# 04_InterfaceSensor.net
KiCad netlist of a schematic drawn in Altium Designer
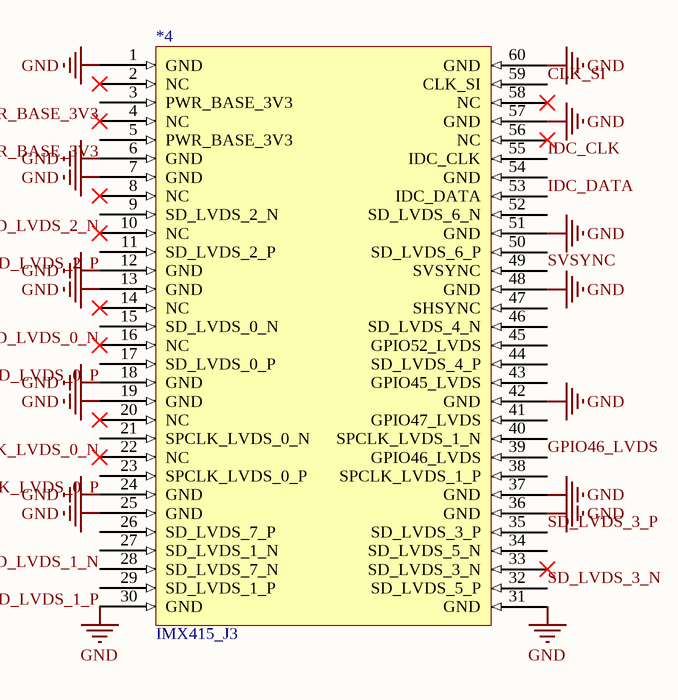
[diagram p0: 04_InterfaceSensor.SchDoc]

(export (version "E")
  (design (tool "Eeschema 10.0.6"))
  (components
    (comp (ref "*4")
      (value "IMX415_J3")
      (footprint "HRS_DF40HC(4.0)-60DS-0.4V(51)")
      (libsource (lib "MyLib") (part "IMX415_J3"))
    )
  )
  (nets
    (net (code "1") (name "/CLK_SI") (class "Default")
      (node (ref "*4") (pin "59") (pinfunction "CLK_SI_59") (pintype "input"))
    )
    (net (code "2") (name "/GPIO46_LVDS") (class "Default")
      (node (ref "*4") (pin "39") (pinfunction "GPIO46_LVDS_39") (pintype "input"))
    )
    (net (code "3") (name "/IDC_CLK") (class "Default")
      (node (ref "*4") (pin "55") (pinfunction "IDC_CLK_55") (pintype "input"))
    )
    (net (code "4") (name "/IDC_DATA") (class "Default")
      (node (ref "*4") (pin "53") (pinfunction "IDC_DATA_53") (pintype "input"))
    )
    (net (code "5") (name "/PWR_BASE_3V3") (class "Default")
      (node (ref "*4") (pin "3") (pinfunction "PWR_BASE_3V3_3") (pintype "input"))
      (node (ref "*4") (pin "5") (pinfunction "PWR_BASE_3V3_5") (pintype "input"))
    )
    (net (code "6") (name "/SD_LVDS_0_N") (class "Default")
      (node (ref "*4") (pin "15") (pinfunction "SD_LVDS_0_N_15") (pintype "input"))
    )
    (net (code "7") (name "/SD_LVDS_0_P") (class "Default")
      (node (ref "*4") (pin "17") (pinfunction "SD_LVDS_0_P_17") (pintype "input"))
    )
    (net (code "8") (name "/SD_LVDS_1_N") (class "Default")
      (node (ref "*4") (pin "27") (pinfunction "SD_LVDS_1_N_27") (pintype "input"))
    )
    (net (code "9") (name "/SD_LVDS_1_P") (class "Default")
      (node (ref "*4") (pin "29") (pinfunction "SD_LVDS_1_P_29") (pintype "input"))
    )
    (net (code "10") (name "/SD_LVDS_2_N") (class "Default")
      (node (ref "*4") (pin "9") (pinfunction "SD_LVDS_2_N_9") (pintype "input"))
    )
    (net (code "11") (name "/SD_LVDS_2_P") (class "Default")
      (node (ref "*4") (pin "11") (pinfunction "SD_LVDS_2_P_11") (pintype "input"))
    )
    (net (code "12") (name "/SD_LVDS_3_N") (class "Default")
      (node (ref "*4") (pin "32") (pinfunction "SD_LVDS_5_P_32") (pintype "input"))
    )
    (net (code "13") (name "/SD_LVDS_3_P") (class "Default")
      (node (ref "*4") (pin "35") (pinfunction "SD_LVDS_3_P_35") (pintype "input"))
    )
    (net (code "14") (name "/SPCLK_LVDS_0_N") (class "Default")
      (node (ref "*4") (pin "21") (pinfunction "SPCLK_LVDS_0_N_21") (pintype "input"))
    )
    (net (code "15") (name "/SPCLK_LVDS_0_P") (class "Default")
      (node (ref "*4") (pin "23") (pinfunction "SPCLK_LVDS_0_P_23") (pintype "input"))
    )
    (net (code "16") (name "/SVSYNC") (class "Default")
      (node (ref "*4") (pin "49") (pinfunction "SVSYNC_49") (pintype "input"))
    )
    (net (code "17") (name "GND") (class "Default")
      (node (ref "*4") (pin "1") (pinfunction "GND_1") (pintype "input"))
      (node (ref "*4") (pin "12") (pinfunction "GND_12") (pintype "input"))
      (node (ref "*4") (pin "13") (pinfunction "GND_13") (pintype "input"))
      (node (ref "*4") (pin "18") (pinfunction "GND_18") (pintype "input"))
      (node (ref "*4") (pin "19") (pinfunction "GND_19") (pintype "input"))
      (node (ref "*4") (pin "24") (pinfunction "GND_24") (pintype "input"))
      (node (ref "*4") (pin "25") (pinfunction "GND_25") (pintype "input"))
      (node (ref "*4") (pin "30") (pinfunction "GND_30") (pintype "input"))
      (node (ref "*4") (pin "31") (pinfunction "GND_31") (pintype "input"))
      (node (ref "*4") (pin "36") (pinfunction "GND_36") (pintype "input"))
      (node (ref "*4") (pin "37") (pinfunction "GND_37") (pintype "input"))
      (node (ref "*4") (pin "42") (pinfunction "GND_42") (pintype "input"))
      (node (ref "*4") (pin "48") (pinfunction "GND_48") (pintype "input"))
      (node (ref "*4") (pin "51") (pinfunction "GND_51") (pintype "input"))
      (node (ref "*4") (pin "57") (pinfunction "GND_57") (pintype "input"))
      (node (ref "*4") (pin "6") (pinfunction "GND_6") (pintype "input"))
      (node (ref "*4") (pin "60") (pinfunction "GND_60") (pintype "input"))
      (node (ref "*4") (pin "7") (pinfunction "GND_7") (pintype "input"))
    )
    (net (code "18") (name "unconnected-(*4-GND-Pad54)") (class "Default")
      (node (ref "*4") (pin "54") (pinfunction "GND_54") (pintype "input"))
    )
    (net (code "19") (name "unconnected-(*4-GPIO45_LVDS-Pad43)") (class "Default")
      (node (ref "*4") (pin "43") (pinfunction "GPIO45_LVDS_43") (pintype "input"))
    )
    (net (code "20") (name "unconnected-(*4-GPIO47_LVDS-Pad41)") (class "Default")
      (node (ref "*4") (pin "41") (pinfunction "GPIO47_LVDS_41") (pintype "input"))
    )
    (net (code "21") (name "unconnected-(*4-GPIO52_LVDS-Pad45)") (class "Default")
      (node (ref "*4") (pin "45") (pinfunction "GPIO52_LVDS_45") (pintype "input"))
    )
    (net (code "22") (name "unconnected-(*4-NC-Pad2)") (class "Default")
      (node (ref "*4") (pin "2") (pinfunction "NC_2") (pintype "input+no_connect"))
    )
    (net (code "23") (name "unconnected-(*4-NC-Pad4)") (class "Default")
      (node (ref "*4") (pin "4") (pinfunction "NC_4") (pintype "input+no_connect"))
    )
    (net (code "24") (name "unconnected-(*4-NC-Pad8)") (class "Default")
      (node (ref "*4") (pin "8") (pinfunction "NC_8") (pintype "input+no_connect"))
    )
    (net (code "25") (name "unconnected-(*4-NC-Pad10)") (class "Default")
      (node (ref "*4") (pin "10") (pinfunction "NC_10") (pintype "input+no_connect"))
    )
    (net (code "26") (name "unconnected-(*4-NC-Pad14)") (class "Default")
      (node (ref "*4") (pin "14") (pinfunction "NC_14") (pintype "input+no_connect"))
    )
    (net (code "27") (name "unconnected-(*4-NC-Pad16)") (class "Default")
      (node (ref "*4") (pin "16") (pinfunction "NC_16") (pintype "input+no_connect"))
    )
    (net (code "28") (name "unconnected-(*4-NC-Pad20)") (class "Default")
      (node (ref "*4") (pin "20") (pinfunction "NC_20") (pintype "input+no_connect"))
    )
    (net (code "29") (name "unconnected-(*4-NC-Pad22)") (class "Default")
      (node (ref "*4") (pin "22") (pinfunction "NC_22") (pintype "input+no_connect"))
    )
    (net (code "30") (name "unconnected-(*4-NC-Pad56)") (class "Default")
      (node (ref "*4") (pin "56") (pinfunction "NC_56") (pintype "input+no_connect"))
    )
    (net (code "31") (name "unconnected-(*4-NC-Pad58)") (class "Default")
      (node (ref "*4") (pin "58") (pinfunction "NC_58") (pintype "input+no_connect"))
    )
    (net (code "32") (name "unconnected-(*4-SD_LVDS_3_N-Pad33)") (class "Default")
      (node (ref "*4") (pin "33") (pinfunction "SD_LVDS_3_N_33") (pintype "input+no_connect"))
    )
    (net (code "33") (name "unconnected-(*4-SD_LVDS_4_N-Pad46)") (class "Default")
      (node (ref "*4") (pin "46") (pinfunction "SD_LVDS_4_N_46") (pintype "input"))
    )
    (net (code "34") (name "unconnected-(*4-SD_LVDS_4_P-Pad44)") (class "Default")
      (node (ref "*4") (pin "44") (pinfunction "SD_LVDS_4_P_44") (pintype "input"))
    )
    (net (code "35") (name "unconnected-(*4-SD_LVDS_5_N-Pad34)") (class "Default")
      (node (ref "*4") (pin "34") (pinfunction "SD_LVDS_5_N_34") (pintype "input"))
    )
    (net (code "36") (name "unconnected-(*4-SD_LVDS_6_N-Pad52)") (class "Default")
      (node (ref "*4") (pin "52") (pinfunction "SD_LVDS_6_N_52") (pintype "input"))
    )
    (net (code "37") (name "unconnected-(*4-SD_LVDS_6_P-Pad50)") (class "Default")
      (node (ref "*4") (pin "50") (pinfunction "SD_LVDS_6_P_50") (pintype "input"))
    )
    (net (code "38") (name "unconnected-(*4-SD_LVDS_7_N-Pad28)") (class "Default")
      (node (ref "*4") (pin "28") (pinfunction "SD_LVDS_7_N_28") (pintype "input"))
    )
    (net (code "39") (name "unconnected-(*4-SD_LVDS_7_P-Pad26)") (class "Default")
      (node (ref "*4") (pin "26") (pinfunction "SD_LVDS_7_P_26") (pintype "input"))
    )
    (net (code "40") (name "unconnected-(*4-SHSYNC-Pad47)") (class "Default")
      (node (ref "*4") (pin "47") (pinfunction "SHSYNC_47") (pintype "input"))
    )
    (net (code "41") (name "unconnected-(*4-SPCLK_LVDS_1_N-Pad40)") (class "Default")
      (node (ref "*4") (pin "40") (pinfunction "SPCLK_LVDS_1_N_40") (pintype "input"))
    )
    (net (code "42") (name "unconnected-(*4-SPCLK_LVDS_1_P-Pad38)") (class "Default")
      (node (ref "*4") (pin "38") (pinfunction "SPCLK_LVDS_1_P_38") (pintype "input"))
    )
  )
)
